# Sheet1.net
KiCad netlist of a schematic drawn in Altium Designer
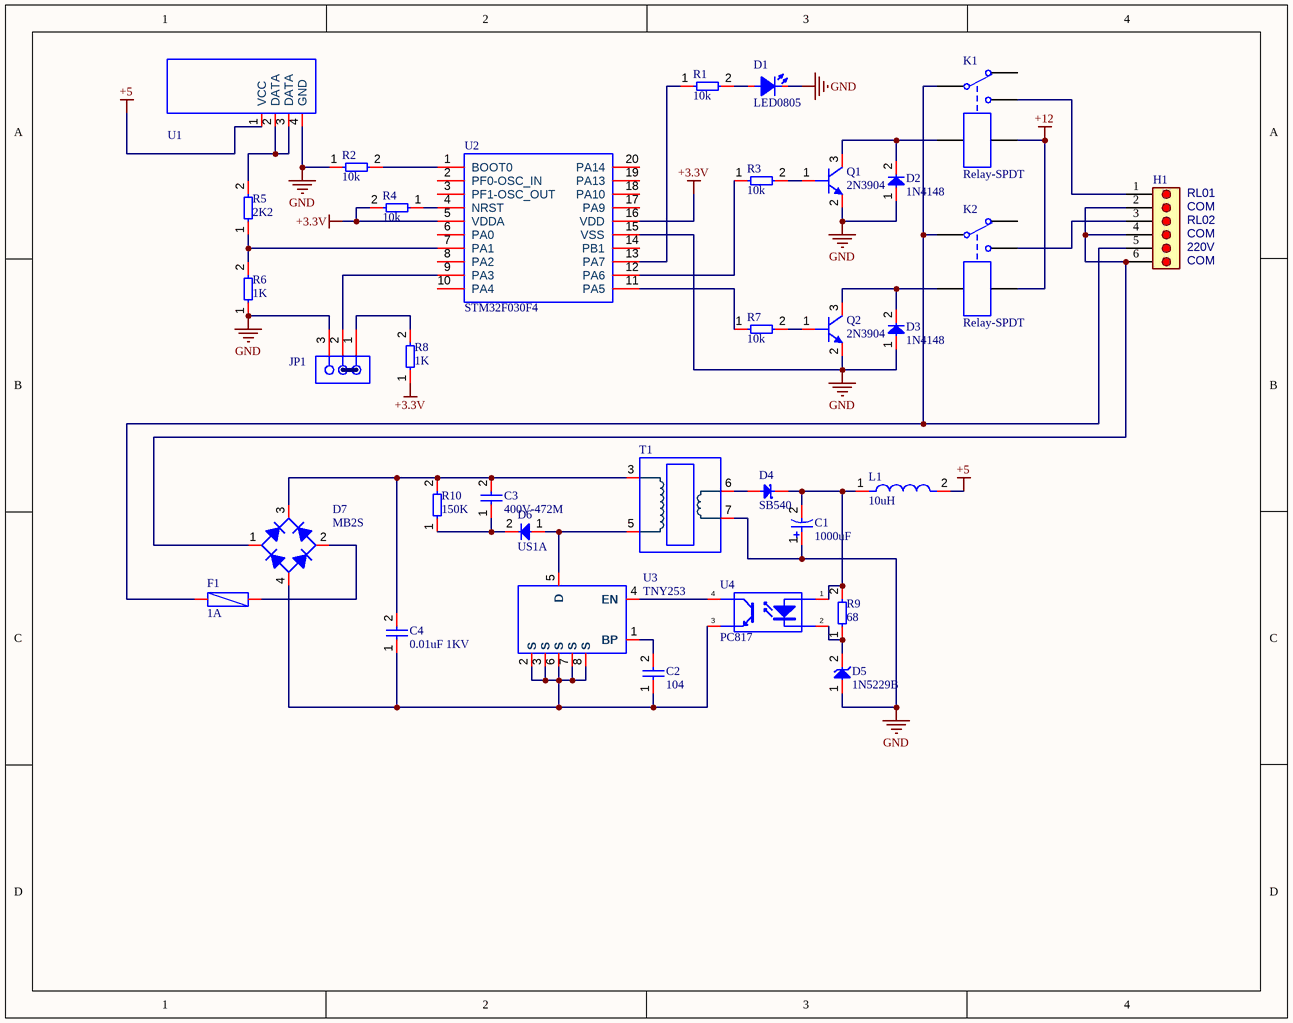
[diagram p0: Sheet1.SchDoc]

(export (version "E")
  (design (tool "Eeschema 10.0.6"))
  (components
    (comp (ref "C1")
      (value "1000uF")
      (footprint "CAP_RAD_4mm")
      (libsource (lib "Lib31082020") (part "Capacitor(Radian)"))
    )
    (comp (ref "C2") (value "104") (footprint "C0805") (libsource (lib "Lib31082020") (part "C0805")))
    (comp (ref "C3") (value "400V-472M") (footprint "C0805") (libsource (lib "Lib31082020") (part "C0805")))
    (comp (ref "C4")
      (value "0.01uF 1KV")
      (footprint "C1812")
      (libsource (lib "Lib31082020") (part "Capacitors(SMD)"))
    )
    (comp (ref "D1")
      (value "LED0805")
      (footprint "L0805RED")
      (libsource (lib "Lib31082020") (part "LED0805"))
    )
    (comp (ref "D2")
      (value "1N4148")
      (footprint "SOD-80")
      (libsource (lib "Lib31082020") (part "1N4148 (SOD-80)"))
    )
    (comp (ref "D3")
      (value "1N4148")
      (footprint "SOD-80")
      (libsource (lib "Lib31082020") (part "1N4148 (SOD-80)"))
    )
    (comp (ref "D4")
      (value "SB540")
      (footprint "DO-214AC(SMA)")
      (libsource (lib "Lib31082020") (part "Diode Schottky"))
    )
    (comp (ref "D5")
      (value "1N5229B")
      (footprint "DO-213AB")
      (libsource (lib "Lib31082020") (part "Diode Zener"))
    )
    (comp (ref "D6")
      (value "US1A")
      (footprint "DO-214AC(SMA)")
      (libsource (lib "Lib31082020") (part "US1A-US1M"))
    )
    (comp (ref "D7")
      (value "MB2S")
      (footprint "TO-269AA")
      (libsource (lib "Lib31082020") (part "Diode MB2S"))
    )
    (comp (ref "F1") (value "1A") (footprint "FUSE1812") (libsource (lib "Lib31082020") (part "Fuse")))
    (comp (ref "H1")
      (value "Header Big 6")
      (footprint "HEADER BIG 6")
      (libsource (lib "Library 3D") (part "Header Big 6"))
    )
    (comp (ref "JP1")
      (value "Header 3x1 TH Pitch 2.54mm")
      (footprint "Header 3x1 TH Pitch 2.54mm")
      (libsource (lib "Lib31082020") (part "Header 3x1 TH Pitch 2.54mm"))
    )
    (comp (ref "K1")
      (value "Relay-SPDT")
      (footprint "RELAY 5A")
      (fields (field (name "PUBLISHER") "Altium Limited"))
      (libsource (lib "Library 3D") (part "Relay-SPDT"))
    )
    (comp (ref "K2")
      (value "Relay-SPDT")
      (footprint "RELAY 5A")
      (fields (field (name "PUBLISHER") "Altium Limited"))
      (libsource (lib "Library 3D") (part "Relay-SPDT"))
    )
    (comp (ref "L1")
      (value "10uH")
      (footprint "INDUCTOR_1206")
      (libsource (lib "Lib31082020") (part "Inductor"))
    )
    (comp (ref "Q1")
      (value "2N3904")
      (footprint "SOT23-3")
      (libsource (lib "Lib31082020") (part "2N3904 (SOT-23)"))
    )
    (comp (ref "Q2")
      (value "2N3904")
      (footprint "SOT23-3")
      (libsource (lib "Lib31082020") (part "2N3904 (SOT-23)"))
    )
    (comp (ref "R1") (value "10k") (footprint "R0805") (libsource (lib "Lib31082020") (part "Resistor SMD")))
    (comp (ref "R2") (value "10k") (footprint "R0805") (libsource (lib "Lib31082020") (part "Resistor SMD")))
    (comp (ref "R3") (value "10k") (footprint "R0805") (libsource (lib "Lib31082020") (part "Resistor SMD")))
    (comp (ref "R4") (value "10k") (footprint "R0805") (libsource (lib "") (part "Resistor SMD_2")))
    (comp (ref "R5") (value "2K2") (footprint "R0805") (libsource (lib "") (part "Resistor SMD_1")))
    (comp (ref "R6") (value "1K") (footprint "R0805") (libsource (lib "") (part "Resistor SMD_1")))
    (comp (ref "R7") (value "10k") (footprint "R0805") (libsource (lib "Lib31082020") (part "Resistor SMD")))
    (comp (ref "R8") (value "1K") (footprint "R0805") (libsource (lib "") (part "Resistor SMD_1")))
    (comp (ref "R9") (value "68") (footprint "R0805") (libsource (lib "") (part "Resistor SMD_1")))
    (comp (ref "R10") (value "150K") (footprint "R0805") (libsource (lib "") (part "Resistor SMD_1")))
    (comp (ref "T1")
      (value "TRANSFORMER_EE16A")
      (footprint "TRANSFORMER_EE16A")
      (libsource (lib "Lib31082020") (part "TRANSFORMER_EE16A"))
    )
    (comp (ref "U1")
      (value "RF433_315_RECEVICE")
      (footprint "RF433_315_RECEVICE")
      (libsource (lib "Lib31082020") (part "RF433_315"))
    )
    (comp (ref "U2")
      (value "STM32F030F4")
      (footprint "TSSOP20_0.65_4.4")
      (description "4Kbyte RAM and 16Kb FLASH")
      (libsource (lib "Lib31082020") (part "STM32F030F4"))
    )
    (comp (ref "U3")
      (value "TNY253")
      (footprint "SOIC08_1.27_6.0")
      (libsource (lib "Lib31082020") (part "TNY253"))
    )
    (comp (ref "U4") (value "PC817") (footprint "DIP4") (libsource (lib "Lib31082020") (part "PC817")))
  )
  (nets
    (net (code "1") (name "+3.3V") (class "Default")
      (node (ref "R4") (pin "2") (pinfunction "2_2") (pintype "passive"))
      (node (ref "R8") (pin "1") (pinfunction "1_1") (pintype "passive"))
      (node (ref "U2") (pin "16") (pinfunction "VDD_16") (pintype "passive"))
      (node (ref "U2") (pin "5") (pinfunction "VDDA_5") (pintype "passive"))
    )
    (net (code "2") (name "+5") (class "Default")
      (node (ref "L1") (pin "2") (pinfunction "2_2") (pintype "passive"))
      (node (ref "U1") (pin "1") (pinfunction "VCC_1") (pintype "passive"))
    )
    (net (code "3") (name "+12") (class "Default")
      (node (ref "K1") (pin "3") (pinfunction "3_3") (pintype "passive"))
      (node (ref "K2") (pin "3") (pinfunction "3_3") (pintype "passive"))
    )
    (net (code "4") (name "GND") (class "Default")
      (node (ref "C1") (pin "1") (pinfunction "1_1") (pintype "passive"))
      (node (ref "D1") (pin "2") (pinfunction "K_2") (pintype "passive"))
      (node (ref "D2") (pin "1") (pinfunction "1_1") (pintype "passive"))
      (node (ref "D3") (pin "1") (pinfunction "1_1") (pintype "passive"))
      (node (ref "D5") (pin "1") (pinfunction "1_1") (pintype "passive"))
      (node (ref "JP1") (pin "3") (pinfunction "3_3") (pintype "passive"))
      (node (ref "Q1") (pin "2") (pinfunction "E_2") (pintype "passive"))
      (node (ref "Q2") (pin "2") (pinfunction "E_2") (pintype "passive"))
      (node (ref "R2") (pin "1") (pinfunction "1_1") (pintype "passive"))
      (node (ref "R6") (pin "1") (pinfunction "1_1") (pintype "passive"))
      (node (ref "T1") (pin "7") (pinfunction "6_7") (pintype "passive"))
      (node (ref "U1") (pin "4") (pinfunction "GND_4") (pintype "passive"))
      (node (ref "U2") (pin "15") (pinfunction "VSS_15") (pintype "passive"))
    )
    (net (code "5") (name "Net-(C3-Pad1)") (class "Default")
      (node (ref "C3") (pin "1") (pinfunction "1_1") (pintype "passive"))
      (node (ref "D6") (pin "2") (pinfunction "2_2") (pintype "passive"))
      (node (ref "R10") (pin "1") (pinfunction "1_1") (pintype "passive"))
    )
    (net (code "6") (name "Net-(C3-Pad2)") (class "Default")
      (node (ref "C3") (pin "2") (pinfunction "2_2") (pintype "passive"))
      (node (ref "C4") (pin "2") (pinfunction "2_2") (pintype "passive"))
      (node (ref "D7") (pin "3") (pinfunction "3_3") (pintype "passive"))
      (node (ref "R10") (pin "2") (pinfunction "2_2") (pintype "passive"))
      (node (ref "T1") (pin "3") (pinfunction "3_3") (pintype "passive"))
    )
    (net (code "7") (name "Net-(D1-A)") (class "Default")
      (node (ref "D1") (pin "1") (pinfunction "A_1") (pintype "passive"))
      (node (ref "R1") (pin "2") (pinfunction "2_2") (pintype "passive"))
    )
    (net (code "8") (name "Net-(D4-A)") (class "Default")
      (node (ref "D4") (pin "1") (pinfunction "A_1") (pintype "passive"))
      (node (ref "T1") (pin "6") (pinfunction "6_6") (pintype "passive"))
    )
    (net (code "9") (name "Net-(D4-K)") (class "Default")
      (node (ref "C1") (pin "2") (pinfunction "2_2") (pintype "passive"))
      (node (ref "D4") (pin "2") (pinfunction "K_2") (pintype "passive"))
      (node (ref "L1") (pin "1") (pinfunction "1_1") (pintype "passive"))
      (node (ref "R9") (pin "2") (pinfunction "2_2") (pintype "passive"))
      (node (ref "U4") (pin "1") (pinfunction "A_1") (pintype "passive"))
    )
    (net (code "10") (name "Net-(D7-Pad1)") (class "Default")
      (node (ref "D7") (pin "1") (pinfunction "1_1") (pintype "passive"))
      (node (ref "H1") (pin "2") (pinfunction "2_2") (pintype "passive"))
      (node (ref "H1") (pin "4") (pinfunction "4_4") (pintype "passive"))
      (node (ref "H1") (pin "6") (pinfunction "6_6") (pintype "passive"))
    )
    (net (code "11") (name "Net-(D7-Pad2)") (class "Default")
      (node (ref "D7") (pin "2") (pinfunction "2_2") (pintype "passive"))
      (node (ref "F1") (pin "2") (pinfunction "2_2") (pintype "passive"))
    )
    (net (code "12") (name "Net-(F1-Pad1)") (class "Default")
      (node (ref "F1") (pin "1") (pinfunction "1_1") (pintype "passive"))
      (node (ref "H1") (pin "5") (pinfunction "5_5") (pintype "passive"))
      (node (ref "K1") (pin "2") (pinfunction "2_2") (pintype "passive"))
      (node (ref "K2") (pin "2") (pinfunction "2_2") (pintype "passive"))
    )
    (net (code "13") (name "Net-(H1-Pad1)") (class "Default")
      (node (ref "H1") (pin "1") (pinfunction "1_1") (pintype "passive"))
      (node (ref "K1") (pin "5") (pinfunction "5_5") (pintype "passive"))
    )
    (net (code "14") (name "Net-(H1-Pad3)") (class "Default")
      (node (ref "H1") (pin "3") (pinfunction "3_3") (pintype "passive"))
      (node (ref "K2") (pin "5") (pinfunction "5_5") (pintype "passive"))
    )
    (net (code "15") (name "Net-(JP1-Pad1)") (class "Default")
      (node (ref "JP1") (pin "1") (pinfunction "1_1") (pintype "passive"))
      (node (ref "R8") (pin "2") (pinfunction "2_2") (pintype "passive"))
    )
    (net (code "16") (name "Net-(Q1-B)") (class "Default")
      (node (ref "Q1") (pin "1") (pinfunction "B_1") (pintype "passive"))
      (node (ref "R3") (pin "2") (pinfunction "2_2") (pintype "passive"))
    )
    (net (code "17") (name "Net-(Q1-C)") (class "Default")
      (node (ref "D2") (pin "2") (pinfunction "2_2") (pintype "passive"))
      (node (ref "K1") (pin "1") (pinfunction "1_1") (pintype "passive"))
      (node (ref "Q1") (pin "3") (pinfunction "C_3") (pintype "passive"))
    )
    (net (code "18") (name "Net-(Q2-B)") (class "Default")
      (node (ref "Q2") (pin "1") (pinfunction "B_1") (pintype "passive"))
      (node (ref "R7") (pin "2") (pinfunction "2_2") (pintype "passive"))
    )
    (net (code "19") (name "Net-(Q2-C)") (class "Default")
      (node (ref "D3") (pin "2") (pinfunction "2_2") (pintype "passive"))
      (node (ref "K2") (pin "1") (pinfunction "1_1") (pintype "passive"))
      (node (ref "Q2") (pin "3") (pinfunction "C_3") (pintype "passive"))
    )
    (net (code "20") (name "Net-(R5-Pad2)") (class "Default")
      (node (ref "R5") (pin "2") (pinfunction "2_2") (pintype "passive"))
      (node (ref "U1") (pin "2") (pinfunction "DATA_2") (pintype "passive"))
      (node (ref "U1") (pin "3") (pinfunction "DATA_3") (pintype "passive"))
    )
    (net (code "21") (name "Net-(U2-BOOT0)") (class "Default")
      (node (ref "R2") (pin "2") (pinfunction "2_2") (pintype "passive"))
      (node (ref "U2") (pin "1") (pinfunction "BOOT0_1") (pintype "passive"))
    )
    (net (code "22") (name "Net-(U2-NRST)") (class "Default")
      (node (ref "R4") (pin "1") (pinfunction "1_1") (pintype "passive"))
      (node (ref "U2") (pin "4") (pinfunction "NRST_4") (pintype "passive"))
    )
    (net (code "23") (name "Net-(U2-PA1)") (class "Default")
      (node (ref "R5") (pin "1") (pinfunction "1_1") (pintype "passive"))
      (node (ref "R6") (pin "2") (pinfunction "2_2") (pintype "passive"))
      (node (ref "U2") (pin "7") (pinfunction "PA1_7") (pintype "passive"))
    )
    (net (code "24") (name "Net-(U2-PA3)") (class "Default")
      (node (ref "JP1") (pin "2") (pinfunction "2_2") (pintype "passive"))
      (node (ref "U2") (pin "9") (pinfunction "PA3_9") (pintype "passive"))
    )
    (net (code "25") (name "Net-(U2-PA5)") (class "Default")
      (node (ref "R7") (pin "1") (pinfunction "1_1") (pintype "passive"))
      (node (ref "U2") (pin "11") (pinfunction "PA5_11") (pintype "passive"))
    )
    (net (code "26") (name "Net-(U2-PA6)") (class "Default")
      (node (ref "R3") (pin "1") (pinfunction "1_1") (pintype "passive"))
      (node (ref "U2") (pin "12") (pinfunction "PA6_12") (pintype "passive"))
    )
    (net (code "27") (name "Net-(U2-PA7)") (class "Default")
      (node (ref "R1") (pin "1") (pinfunction "1_1") (pintype "passive"))
      (node (ref "U2") (pin "13") (pinfunction "PA7_13") (pintype "passive"))
    )
    (net (code "28") (name "Net-(U3-BP)") (class "Default")
      (node (ref "C2") (pin "2") (pinfunction "2_2") (pintype "passive"))
      (node (ref "U3") (pin "1") (pinfunction "BP_1") (pintype "passive"))
    )
    (net (code "29") (name "Net-(U3-D)") (class "Default")
      (node (ref "D6") (pin "1") (pinfunction "1_1") (pintype "passive"))
      (node (ref "T1") (pin "5") (pinfunction "5_5") (pintype "passive"))
      (node (ref "U3") (pin "5") (pinfunction "D_5") (pintype "passive"))
    )
    (net (code "30") (name "Net-(U3-EN)") (class "Default")
      (node (ref "U3") (pin "4") (pinfunction "EN_4") (pintype "passive"))
      (node (ref "U4") (pin "4") (pinfunction "C_4") (pintype "passive"))
    )
    (net (code "31") (name "Net-(U4-E)") (class "Default")
      (node (ref "C2") (pin "1") (pinfunction "1_1") (pintype "passive"))
      (node (ref "C4") (pin "1") (pinfunction "1_1") (pintype "passive"))
      (node (ref "D7") (pin "4") (pinfunction "4_4") (pintype "passive"))
      (node (ref "U3") (pin "2") (pinfunction "S_2") (pintype "passive"))
      (node (ref "U3") (pin "3") (pinfunction "S_3") (pintype "passive"))
      (node (ref "U3") (pin "6") (pinfunction "S_6") (pintype "passive"))
      (node (ref "U3") (pin "7") (pinfunction "S_7") (pintype "passive"))
      (node (ref "U3") (pin "8") (pinfunction "S_8") (pintype "passive"))
      (node (ref "U4") (pin "3") (pinfunction "E_3") (pintype "passive"))
    )
    (net (code "32") (name "Net-(U4-K)") (class "Default")
      (node (ref "D5") (pin "2") (pinfunction "2_2") (pintype "passive"))
      (node (ref "R9") (pin "1") (pinfunction "1_1") (pintype "passive"))
      (node (ref "U4") (pin "2") (pinfunction "K_2") (pintype "passive"))
    )
    (net (code "33") (name "unconnected-(K1-Pad4)") (class "Default")
      (node (ref "K1") (pin "4") (pinfunction "4_4") (pintype "passive"))
    )
    (net (code "34") (name "unconnected-(K2-Pad4)") (class "Default")
      (node (ref "K2") (pin "4") (pinfunction "4_4") (pintype "passive"))
    )
    (net (code "35") (name "unconnected-(U2-PA0-Pad6)") (class "Default")
      (node (ref "U2") (pin "6") (pinfunction "PA0_6") (pintype "passive"))
    )
    (net (code "36") (name "unconnected-(U2-PA2-Pad8)") (class "Default")
      (node (ref "U2") (pin "8") (pinfunction "PA2_8") (pintype "passive"))
    )
    (net (code "37") (name "unconnected-(U2-PA4-Pad10)") (class "Default")
      (node (ref "U2") (pin "10") (pinfunction "PA4_10") (pintype "passive"))
    )
    (net (code "38") (name "unconnected-(U2-PA9-Pad17)") (class "Default")
      (node (ref "U2") (pin "17") (pinfunction "PA9_17") (pintype "passive"))
    )
    (net (code "39") (name "unconnected-(U2-PA10-Pad18)") (class "Default")
      (node (ref "U2") (pin "18") (pinfunction "PA10_18") (pintype "passive"))
    )
    (net (code "40") (name "unconnected-(U2-PA13-Pad19)") (class "Default")
      (node (ref "U2") (pin "19") (pinfunction "PA13_19") (pintype "passive"))
    )
    (net (code "41") (name "unconnected-(U2-PA14-Pad20)") (class "Default")
      (node (ref "U2") (pin "20") (pinfunction "PA14_20") (pintype "passive"))
    )
    (net (code "42") (name "unconnected-(U2-PB1-Pad14)") (class "Default")
      (node (ref "U2") (pin "14") (pinfunction "PB1_14") (pintype "passive"))
    )
    (net (code "43") (name "unconnected-(U2-PF0-OSC_IN-Pad2)") (class "Default")
      (node (ref "U2") (pin "2") (pinfunction "PF0-OSC_IN_2") (pintype "passive"))
    )
    (net (code "44") (name "unconnected-(U2-PF1-OSC_OUT-Pad3)") (class "Default")
      (node (ref "U2") (pin "3") (pinfunction "PF1-OSC_OUT_3") (pintype "passive"))
    )
  )
)
